# schematic.net
KiCad netlist of a schematic drawn in Altium Designer
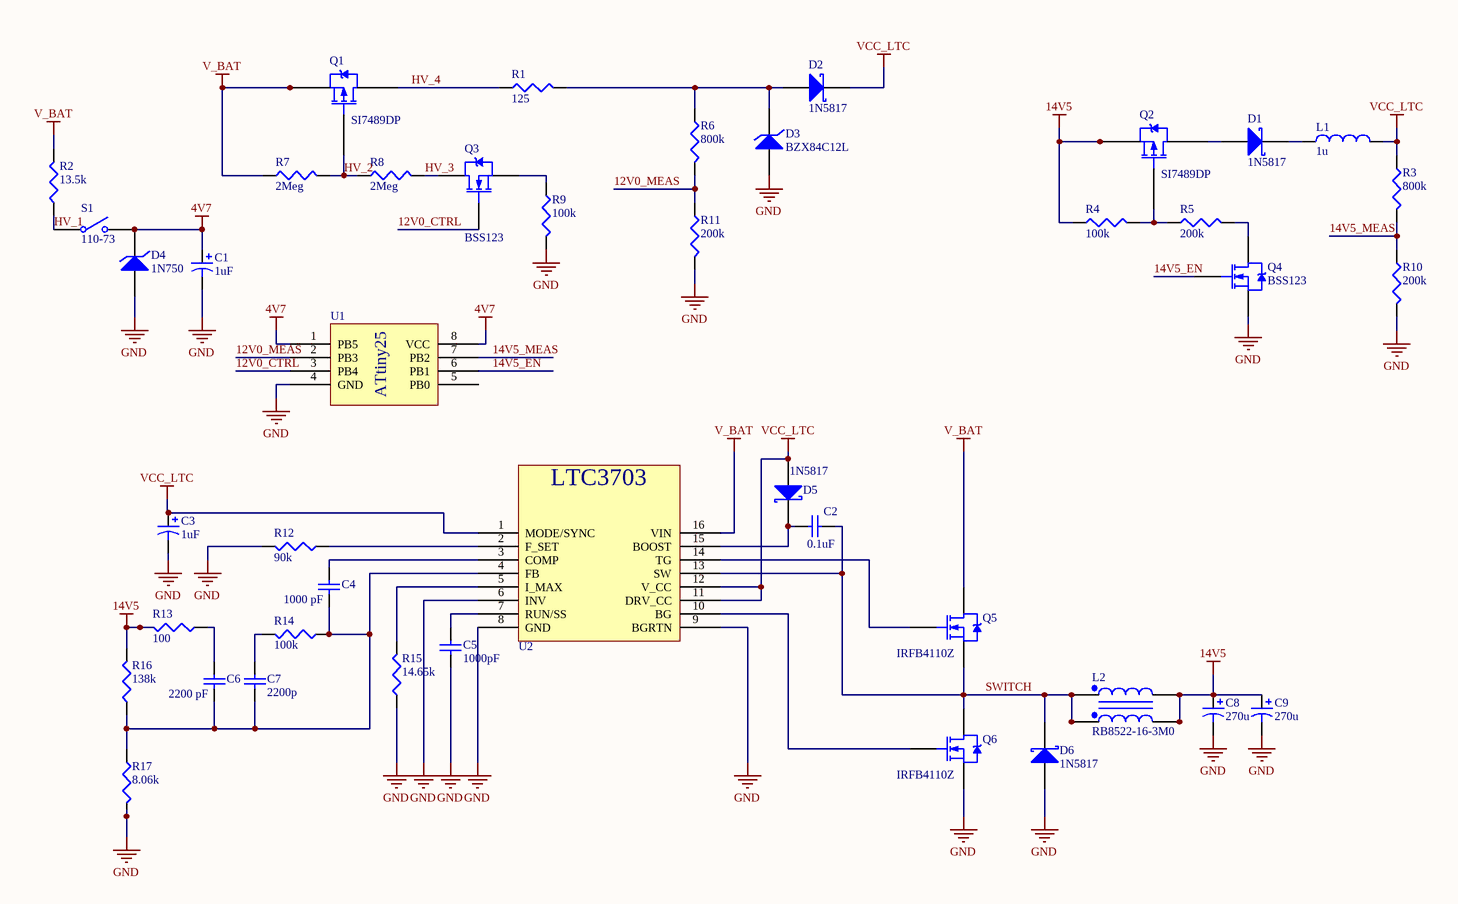
[diagram p0: schematic.SchDoc]

(export (version "E")
  (design (tool "Eeschema 10.0.6"))
  (components
    (comp (ref "C1")
      (value "1uF")
      (footprint "EB Series Type A - 5mm")
      (description "Electrolytic Capacitor")
      (fields (field (name "Comment") "Capacitor-EB Series, Type A"))
      (libsource (lib "company parts") (part "Capacitor-EB Series, Type A"))
    )
    (comp (ref "C2")
      (value "0.1uF")
      (footprint "CAP0805")
      (fields (field (name "Comment") "Capacitor"))
      (libsource (lib "company parts") (part "Capacitor"))
    )
    (comp (ref "C3")
      (value "1uF")
      (footprint "EB Series Type A - 5mm")
      (description "Electrolytic Capacitor")
      (fields (field (name "Comment") "Capacitor-EB Series, Type A"))
      (libsource (lib "company parts") (part "Capacitor-EB Series, Type A"))
    )
    (comp (ref "C4")
      (value "1000 pF")
      (footprint "CAP0805")
      (fields (field (name "Comment") "Capacitor"))
      (libsource (lib "company parts") (part "Capacitor"))
    )
    (comp (ref "C5")
      (value "1000pF")
      (footprint "CAP0805")
      (fields (field (name "Comment") "Capacitor"))
      (libsource (lib "company parts") (part "Capacitor"))
    )
    (comp (ref "C6")
      (value "2200 pF")
      (footprint "CAP0805")
      (fields (field (name "Comment") "Capacitor"))
      (libsource (lib "company parts") (part "Capacitor"))
    )
    (comp (ref "C7")
      (value "2200p")
      (footprint "CAP0805")
      (fields (field (name "Comment") "Capacitor"))
      (libsource (lib "company parts") (part "Capacitor"))
    )
    (comp (ref "C8")
      (value "270u")
      (footprint "EB Series Type A - 8mm")
      (description "Electrolytic Capacitor")
      (fields (field (name "Comment") "Capacitor-EB Series, Type A"))
      (libsource (lib "company parts") (part "Capacitor-EB Series, Type A"))
    )
    (comp (ref "C9")
      (value "270u")
      (footprint "EB Series Type A - 8mm")
      (description "Electrolytic Capacitor")
      (fields (field (name "Comment") "Capacitor-EB Series, Type A"))
      (libsource (lib "company parts") (part "Capacitor-EB Series, Type A"))
    )
    (comp (ref "D1") (value "1N5817") (footprint "DO-41") (libsource (lib "company parts") (part "1N5817")))
    (comp (ref "D2") (value "1N5817") (footprint "DO-41") (libsource (lib "company parts") (part "1N5817")))
    (comp (ref "D3")
      (value "BZX84C12L")
      (footprint "3-Lead SOT-23")
      (libsource (lib "company parts") (part "BZX84C12L"))
    )
    (comp (ref "D4") (value "1N750") (footprint "DO-35") (libsource (lib "symbols") (part "1N750")))
    (comp (ref "D5") (value "1N5817") (footprint "DO-41") (libsource (lib "company parts") (part "1N5817")))
    (comp (ref "D6") (value "1N5817") (footprint "DO-41") (libsource (lib "company parts") (part "1N5817")))
    (comp (ref "L1")
      (value "1u")
      (footprint "RES1206")
      (fields (field (name "Comment") "Inductor"))
      (libsource (lib "company parts") (part "Inductor"))
    )
    (comp (ref "L2")
      (value "RB8522-16-3M0")
      (footprint "RB8522-16-3M0")
      (libsource (lib "company parts") (part "RB8522-16-3M0"))
    )
    (comp (ref "Q1")
      (value "SI7489DP")
      (footprint "PowerPAK SO-8")
      (libsource (lib "company parts") (part "SI7489DP"))
    )
    (comp (ref "Q2")
      (value "SI7489DP")
      (footprint "PowerPAK SO-8")
      (libsource (lib "company parts") (part "SI7489DP"))
    )
    (comp (ref "Q3")
      (value "BSS123")
      (footprint "3-Lead SOT-23")
      (libsource (lib "company parts") (part "BSS123"))
    )
    (comp (ref "Q4")
      (value "BSS123")
      (footprint "3-Lead SOT-23")
      (libsource (lib "company parts") (part "BSS123"))
    )
    (comp (ref "Q5")
      (value "IRFB4110Z")
      (footprint "TO-220")
      (libsource (lib "company parts") (part "IRFB4110Z"))
    )
    (comp (ref "Q6")
      (value "IRFB4110Z")
      (footprint "TO-220")
      (libsource (lib "company parts") (part "IRFB4110Z"))
    )
    (comp (ref "R1")
      (value "125")
      (footprint "RES1206")
      (fields (field (name "Comment") "Resistor"))
      (libsource (lib "company parts") (part "Resistor"))
    )
    (comp (ref "R2")
      (value "13.5k")
      (footprint "RES1206")
      (fields (field (name "Comment") "Resistor"))
      (libsource (lib "company parts") (part "Resistor"))
    )
    (comp (ref "R3")
      (value "800k")
      (footprint "RES0805")
      (fields (field (name "Comment") "Resistor"))
      (libsource (lib "company parts") (part "Resistor"))
    )
    (comp (ref "R4")
      (value "100k")
      (footprint "RES0805")
      (fields (field (name "Comment") "Resistor"))
      (libsource (lib "company parts") (part "Resistor"))
    )
    (comp (ref "R5")
      (value "200k")
      (footprint "RES0805")
      (fields (field (name "Comment") "Resistor"))
      (libsource (lib "company parts") (part "Resistor"))
    )
    (comp (ref "R6")
      (value "800k")
      (footprint "RES0805")
      (fields (field (name "Comment") "Resistor"))
      (libsource (lib "company parts") (part "Resistor"))
    )
    (comp (ref "R7")
      (value "2Meg")
      (footprint "RES0805")
      (fields (field (name "Comment") "Resistor"))
      (libsource (lib "company parts") (part "Resistor"))
    )
    (comp (ref "R8")
      (value "2Meg")
      (footprint "RES0805")
      (fields (field (name "Comment") "Resistor"))
      (libsource (lib "company parts") (part "Resistor"))
    )
    (comp (ref "R9")
      (value "100k")
      (footprint "RES0805")
      (fields (field (name "Comment") "Resistor"))
      (libsource (lib "company parts") (part "Resistor"))
    )
    (comp (ref "R10")
      (value "200k")
      (footprint "RES0805")
      (fields (field (name "Comment") "Resistor"))
      (libsource (lib "company parts") (part "Resistor"))
    )
    (comp (ref "R11")
      (value "200k")
      (footprint "RES0805")
      (fields (field (name "Comment") "Resistor"))
      (libsource (lib "company parts") (part "Resistor"))
    )
    (comp (ref "R12")
      (value "90k")
      (footprint "RES0805")
      (fields (field (name "Comment") "Resistor"))
      (libsource (lib "company parts") (part "Resistor"))
    )
    (comp (ref "R13")
      (value "100")
      (footprint "RES0805")
      (fields (field (name "Comment") "Resistor"))
      (libsource (lib "company parts") (part "Resistor"))
    )
    (comp (ref "R14")
      (value "100k")
      (footprint "RES0805")
      (fields (field (name "Comment") "Resistor"))
      (libsource (lib "company parts") (part "Resistor"))
    )
    (comp (ref "R15")
      (value "14.65k")
      (footprint "RES0805")
      (fields (field (name "Comment") "Resistor"))
      (libsource (lib "company parts") (part "Resistor"))
    )
    (comp (ref "R16")
      (value "138k")
      (footprint "RES0805")
      (fields (field (name "Comment") "Resistor"))
      (libsource (lib "company parts") (part "Resistor"))
    )
    (comp (ref "R17")
      (value "8.06k")
      (footprint "RES0805")
      (fields (field (name "Comment") "Resistor"))
      (libsource (lib "company parts") (part "Resistor"))
    )
    (comp (ref "S1") (value "110-73") (footprint "100-73") (libsource (lib "company parts") (part "110-73")))
    (comp (ref "U1")
      (value "ATtiny25")
      (footprint "PDIP-8")
      (libsource (lib "company parts") (part "ATtiny25"))
    )
    (comp (ref "U2")
      (value "LTC3703")
      (footprint "SSOP-16")
      (libsource (lib "company parts") (part "LTC3703"))
    )
  )
  (nets
    (net (code "1") (name "/12V0_CTRL") (class "Default")
      (node (ref "Q3") (pin "1") (pinfunction "G_1") (pintype "passive"))
      (node (ref "U1") (pin "3") (pinfunction "PB4_3") (pintype "passive"))
    )
    (net (code "2") (name "/12V0_MEAS") (class "Default")
      (node (ref "R11") (pin "1") (pinfunction "1_1") (pintype "passive"))
      (node (ref "R6") (pin "2") (pinfunction "2_2") (pintype "passive"))
      (node (ref "U1") (pin "2") (pinfunction "PB3_2") (pintype "passive"))
    )
    (net (code "3") (name "/14V5_EN") (class "Default")
      (node (ref "Q4") (pin "1") (pinfunction "G_1") (pintype "passive"))
      (node (ref "U1") (pin "6") (pinfunction "PB1_6") (pintype "passive"))
    )
    (net (code "4") (name "/14V5_MEAS") (class "Default")
      (node (ref "R10") (pin "1") (pinfunction "1_1") (pintype "passive"))
      (node (ref "R3") (pin "2") (pinfunction "2_2") (pintype "passive"))
      (node (ref "U1") (pin "7") (pinfunction "PB2_7") (pintype "passive"))
    )
    (net (code "5") (name "/HV_1") (class "Default")
      (node (ref "R2") (pin "1") (pinfunction "1_1") (pintype "passive"))
      (node (ref "S1") (pin "1") (pinfunction "COMMON_1") (pintype "passive"))
    )
    (net (code "6") (name "/HV_2") (class "Default")
      (node (ref "Q1") (pin "4") (pinfunction "G_4") (pintype "passive"))
      (node (ref "R7") (pin "2") (pinfunction "2_2") (pintype "passive"))
      (node (ref "R8") (pin "1") (pinfunction "1_1") (pintype "passive"))
    )
    (net (code "7") (name "/HV_3") (class "Default")
      (node (ref "Q3") (pin "2") (pinfunction "D_2") (pintype "passive"))
      (node (ref "R8") (pin "2") (pinfunction "2_2") (pintype "passive"))
    )
    (net (code "8") (name "/HV_4") (class "Default")
      (node (ref "Q1") (pin "5") (pinfunction "D_5") (pintype "passive"))
      (node (ref "R1") (pin "1") (pinfunction "1_1") (pintype "passive"))
    )
    (net (code "9") (name "/SWITCH") (class "Default")
      (node (ref "C2") (pin "2") (pinfunction "2_2") (pintype "passive"))
      (node (ref "D6") (pin "1") (pinfunction "K_1") (pintype "passive"))
      (node (ref "L2") (pin "1") (pinfunction "1_1") (pintype "passive"))
      (node (ref "L2") (pin "2") (pinfunction "2_2") (pintype "passive"))
      (node (ref "L2") (pin "3") (pinfunction "3_3") (pintype "passive"))
      (node (ref "L2") (pin "4") (pinfunction "4_4") (pintype "passive"))
      (node (ref "Q5") (pin "3") (pinfunction "S_3") (pintype "passive"))
      (node (ref "Q6") (pin "2") (pinfunction "D_2") (pintype "passive"))
      (node (ref "U2") (pin "13") (pinfunction "SW_13") (pintype "passive"))
    )
    (net (code "10") (name "4V7") (class "Default")
      (node (ref "C1") (pin "1") (pinfunction "1_1") (pintype "passive"))
      (node (ref "D4") (pin "1") (pinfunction "K_1") (pintype "passive"))
      (node (ref "S1") (pin "2") (pinfunction "NO_2") (pintype "passive"))
      (node (ref "U1") (pin "1") (pinfunction "PB5_1") (pintype "passive"))
      (node (ref "U1") (pin "8") (pinfunction "VCC_8") (pintype "passive"))
    )
    (net (code "11") (name "14V5") (class "Default")
      (node (ref "C8") (pin "1") (pinfunction "1_1") (pintype "passive"))
      (node (ref "C9") (pin "1") (pinfunction "1_1") (pintype "passive"))
      (node (ref "L2") (pin "5") (pinfunction "5_5") (pintype "passive"))
      (node (ref "L2") (pin "6") (pinfunction "6_6") (pintype "passive"))
      (node (ref "L2") (pin "7") (pinfunction "7_7") (pintype "passive"))
      (node (ref "L2") (pin "8") (pinfunction "8_8") (pintype "passive"))
      (node (ref "Q2") (pin "1") (pinfunction "S_1") (pintype "passive"))
      (node (ref "Q2") (pin "2") (pinfunction "S_2") (pintype "passive"))
      (node (ref "Q2") (pin "3") (pinfunction "S_3") (pintype "passive"))
      (node (ref "R13") (pin "2") (pinfunction "2_2") (pintype "passive"))
      (node (ref "R16") (pin "2") (pinfunction "2_2") (pintype "passive"))
      (node (ref "R4") (pin "1") (pinfunction "1_1") (pintype "passive"))
    )
    (net (code "12") (name "GND") (class "Default")
      (node (ref "C1") (pin "2") (pinfunction "2_2") (pintype "passive"))
      (node (ref "C3") (pin "2") (pinfunction "2_2") (pintype "passive"))
      (node (ref "C5") (pin "1") (pinfunction "1_1") (pintype "passive"))
      (node (ref "C8") (pin "2") (pinfunction "2_2") (pintype "passive"))
      (node (ref "C9") (pin "2") (pinfunction "2_2") (pintype "passive"))
      (node (ref "D3") (pin "1") (pinfunction "A_1") (pintype "passive"))
      (node (ref "D4") (pin "2") (pinfunction "A_2") (pintype "passive"))
      (node (ref "D6") (pin "2") (pinfunction "A_2") (pintype "passive"))
      (node (ref "Q4") (pin "3") (pinfunction "S_3") (pintype "passive"))
      (node (ref "Q6") (pin "3") (pinfunction "S_3") (pintype "passive"))
      (node (ref "R10") (pin "2") (pinfunction "2_2") (pintype "passive"))
      (node (ref "R11") (pin "2") (pinfunction "2_2") (pintype "passive"))
      (node (ref "R12") (pin "2") (pinfunction "2_2") (pintype "passive"))
      (node (ref "R15") (pin "1") (pinfunction "1_1") (pintype "passive"))
      (node (ref "R17") (pin "2") (pinfunction "2_2") (pintype "passive"))
      (node (ref "R9") (pin "2") (pinfunction "2_2") (pintype "passive"))
      (node (ref "U1") (pin "4") (pinfunction "GND_4") (pintype "passive"))
      (node (ref "U2") (pin "6") (pinfunction "INV_6") (pintype "passive"))
      (node (ref "U2") (pin "8") (pinfunction "GND_8") (pintype "passive"))
      (node (ref "U2") (pin "9") (pinfunction "BGRTN_9") (pintype "passive"))
    )
    (net (code "13") (name "Net-(C6-Pad1)") (class "Default")
      (node (ref "C6") (pin "1") (pinfunction "1_1") (pintype "passive"))
      (node (ref "R13") (pin "1") (pinfunction "1_1") (pintype "passive"))
    )
    (net (code "14") (name "Net-(C7-Pad2)") (class "Default")
      (node (ref "C7") (pin "2") (pinfunction "2_2") (pintype "passive"))
      (node (ref "R14") (pin "2") (pinfunction "2_2") (pintype "passive"))
    )
    (net (code "15") (name "Net-(D1-A)") (class "Default")
      (node (ref "D1") (pin "2") (pinfunction "A_2") (pintype "passive"))
      (node (ref "Q2") (pin "5") (pinfunction "D_5") (pintype "passive"))
    )
    (net (code "16") (name "Net-(D1-K)") (class "Default")
      (node (ref "D1") (pin "1") (pinfunction "K_1") (pintype "passive"))
      (node (ref "L1") (pin "1") (pinfunction "1_1") (pintype "passive"))
    )
    (net (code "17") (name "Net-(D2-A)") (class "Default")
      (node (ref "D2") (pin "2") (pinfunction "A_2") (pintype "passive"))
      (node (ref "D3") (pin "3") (pinfunction "K_3") (pintype "passive"))
      (node (ref "R1") (pin "2") (pinfunction "2_2") (pintype "passive"))
      (node (ref "R6") (pin "1") (pinfunction "1_1") (pintype "passive"))
    )
    (net (code "18") (name "Net-(D5-K)") (class "Default")
      (node (ref "C2") (pin "1") (pinfunction "1_1") (pintype "passive"))
      (node (ref "D5") (pin "1") (pinfunction "K_1") (pintype "passive"))
      (node (ref "U2") (pin "15") (pinfunction "BOOST_15") (pintype "passive"))
    )
    (net (code "19") (name "Net-(Q2-G)") (class "Default")
      (node (ref "Q2") (pin "4") (pinfunction "G_4") (pintype "passive"))
      (node (ref "R4") (pin "2") (pinfunction "2_2") (pintype "passive"))
      (node (ref "R5") (pin "1") (pinfunction "1_1") (pintype "passive"))
    )
    (net (code "20") (name "Net-(Q3-S)") (class "Default")
      (node (ref "Q3") (pin "3") (pinfunction "S_3") (pintype "passive"))
      (node (ref "R9") (pin "1") (pinfunction "1_1") (pintype "passive"))
    )
    (net (code "21") (name "Net-(Q4-D)") (class "Default")
      (node (ref "Q4") (pin "2") (pinfunction "D_2") (pintype "passive"))
      (node (ref "R5") (pin "2") (pinfunction "2_2") (pintype "passive"))
    )
    (net (code "22") (name "Net-(Q5-G)") (class "Default")
      (node (ref "Q5") (pin "1") (pinfunction "G_1") (pintype "passive"))
      (node (ref "U2") (pin "14") (pinfunction "TG_14") (pintype "passive"))
    )
    (net (code "23") (name "Net-(Q6-G)") (class "Default")
      (node (ref "Q6") (pin "1") (pinfunction "G_1") (pintype "passive"))
      (node (ref "U2") (pin "10") (pinfunction "BG_10") (pintype "passive"))
    )
    (net (code "24") (name "Net-(U2-COMP)") (class "Default")
      (node (ref "C4") (pin "2") (pinfunction "2_2") (pintype "passive"))
      (node (ref "U2") (pin "3") (pinfunction "COMP_3") (pintype "passive"))
    )
    (net (code "25") (name "Net-(U2-FB)") (class "Default")
      (node (ref "C4") (pin "1") (pinfunction "1_1") (pintype "passive"))
      (node (ref "C6") (pin "2") (pinfunction "2_2") (pintype "passive"))
      (node (ref "C7") (pin "1") (pinfunction "1_1") (pintype "passive"))
      (node (ref "R14") (pin "1") (pinfunction "1_1") (pintype "passive"))
      (node (ref "R16") (pin "1") (pinfunction "1_1") (pintype "passive"))
      (node (ref "R17") (pin "1") (pinfunction "1_1") (pintype "passive"))
      (node (ref "U2") (pin "4") (pinfunction "FB_4") (pintype "passive"))
    )
    (net (code "26") (name "Net-(U2-F_SET)") (class "Default")
      (node (ref "R12") (pin "1") (pinfunction "1_1") (pintype "passive"))
      (node (ref "U2") (pin "2") (pinfunction "F_SET_2") (pintype "passive"))
    )
    (net (code "27") (name "Net-(U2-I_MAX)") (class "Default")
      (node (ref "R15") (pin "2") (pinfunction "2_2") (pintype "passive"))
      (node (ref "U2") (pin "5") (pinfunction "I_MAX_5") (pintype "passive"))
    )
    (net (code "28") (name "Net-(U2-RUN{slash}SS)") (class "Default")
      (node (ref "C5") (pin "2") (pinfunction "2_2") (pintype "passive"))
      (node (ref "U2") (pin "7") (pinfunction "RUN/SS_7") (pintype "passive"))
    )
    (net (code "29") (name "VCC_LTC") (class "Default")
      (node (ref "C3") (pin "1") (pinfunction "1_1") (pintype "passive"))
      (node (ref "D2") (pin "1") (pinfunction "K_1") (pintype "passive"))
      (node (ref "D5") (pin "2") (pinfunction "A_2") (pintype "passive"))
      (node (ref "L1") (pin "2") (pinfunction "2_2") (pintype "passive"))
      (node (ref "R3") (pin "1") (pinfunction "1_1") (pintype "passive"))
      (node (ref "U2") (pin "1") (pinfunction "MODE/SYNC_1") (pintype "passive"))
      (node (ref "U2") (pin "11") (pinfunction "DRV_CC_11") (pintype "passive"))
      (node (ref "U2") (pin "12") (pinfunction "V_CC_12") (pintype "passive"))
    )
    (net (code "30") (name "V_BAT") (class "Default")
      (node (ref "Q1") (pin "1") (pinfunction "S_1") (pintype "passive"))
      (node (ref "Q1") (pin "2") (pinfunction "S_2") (pintype "passive"))
      (node (ref "Q1") (pin "3") (pinfunction "S_3") (pintype "passive"))
      (node (ref "Q5") (pin "2") (pinfunction "D_2") (pintype "passive"))
      (node (ref "R2") (pin "2") (pinfunction "2_2") (pintype "passive"))
      (node (ref "R7") (pin "1") (pinfunction "1_1") (pintype "passive"))
      (node (ref "U2") (pin "16") (pinfunction "VIN_16") (pintype "passive"))
    )
    (net (code "31") (name "unconnected-(U1-PB0-Pad5)") (class "Default")
      (node (ref "U1") (pin "5") (pinfunction "PB0_5") (pintype "passive"))
    )
  )
)
